# H15R80.net
KiCad netlist of a schematic drawn in EAGLE
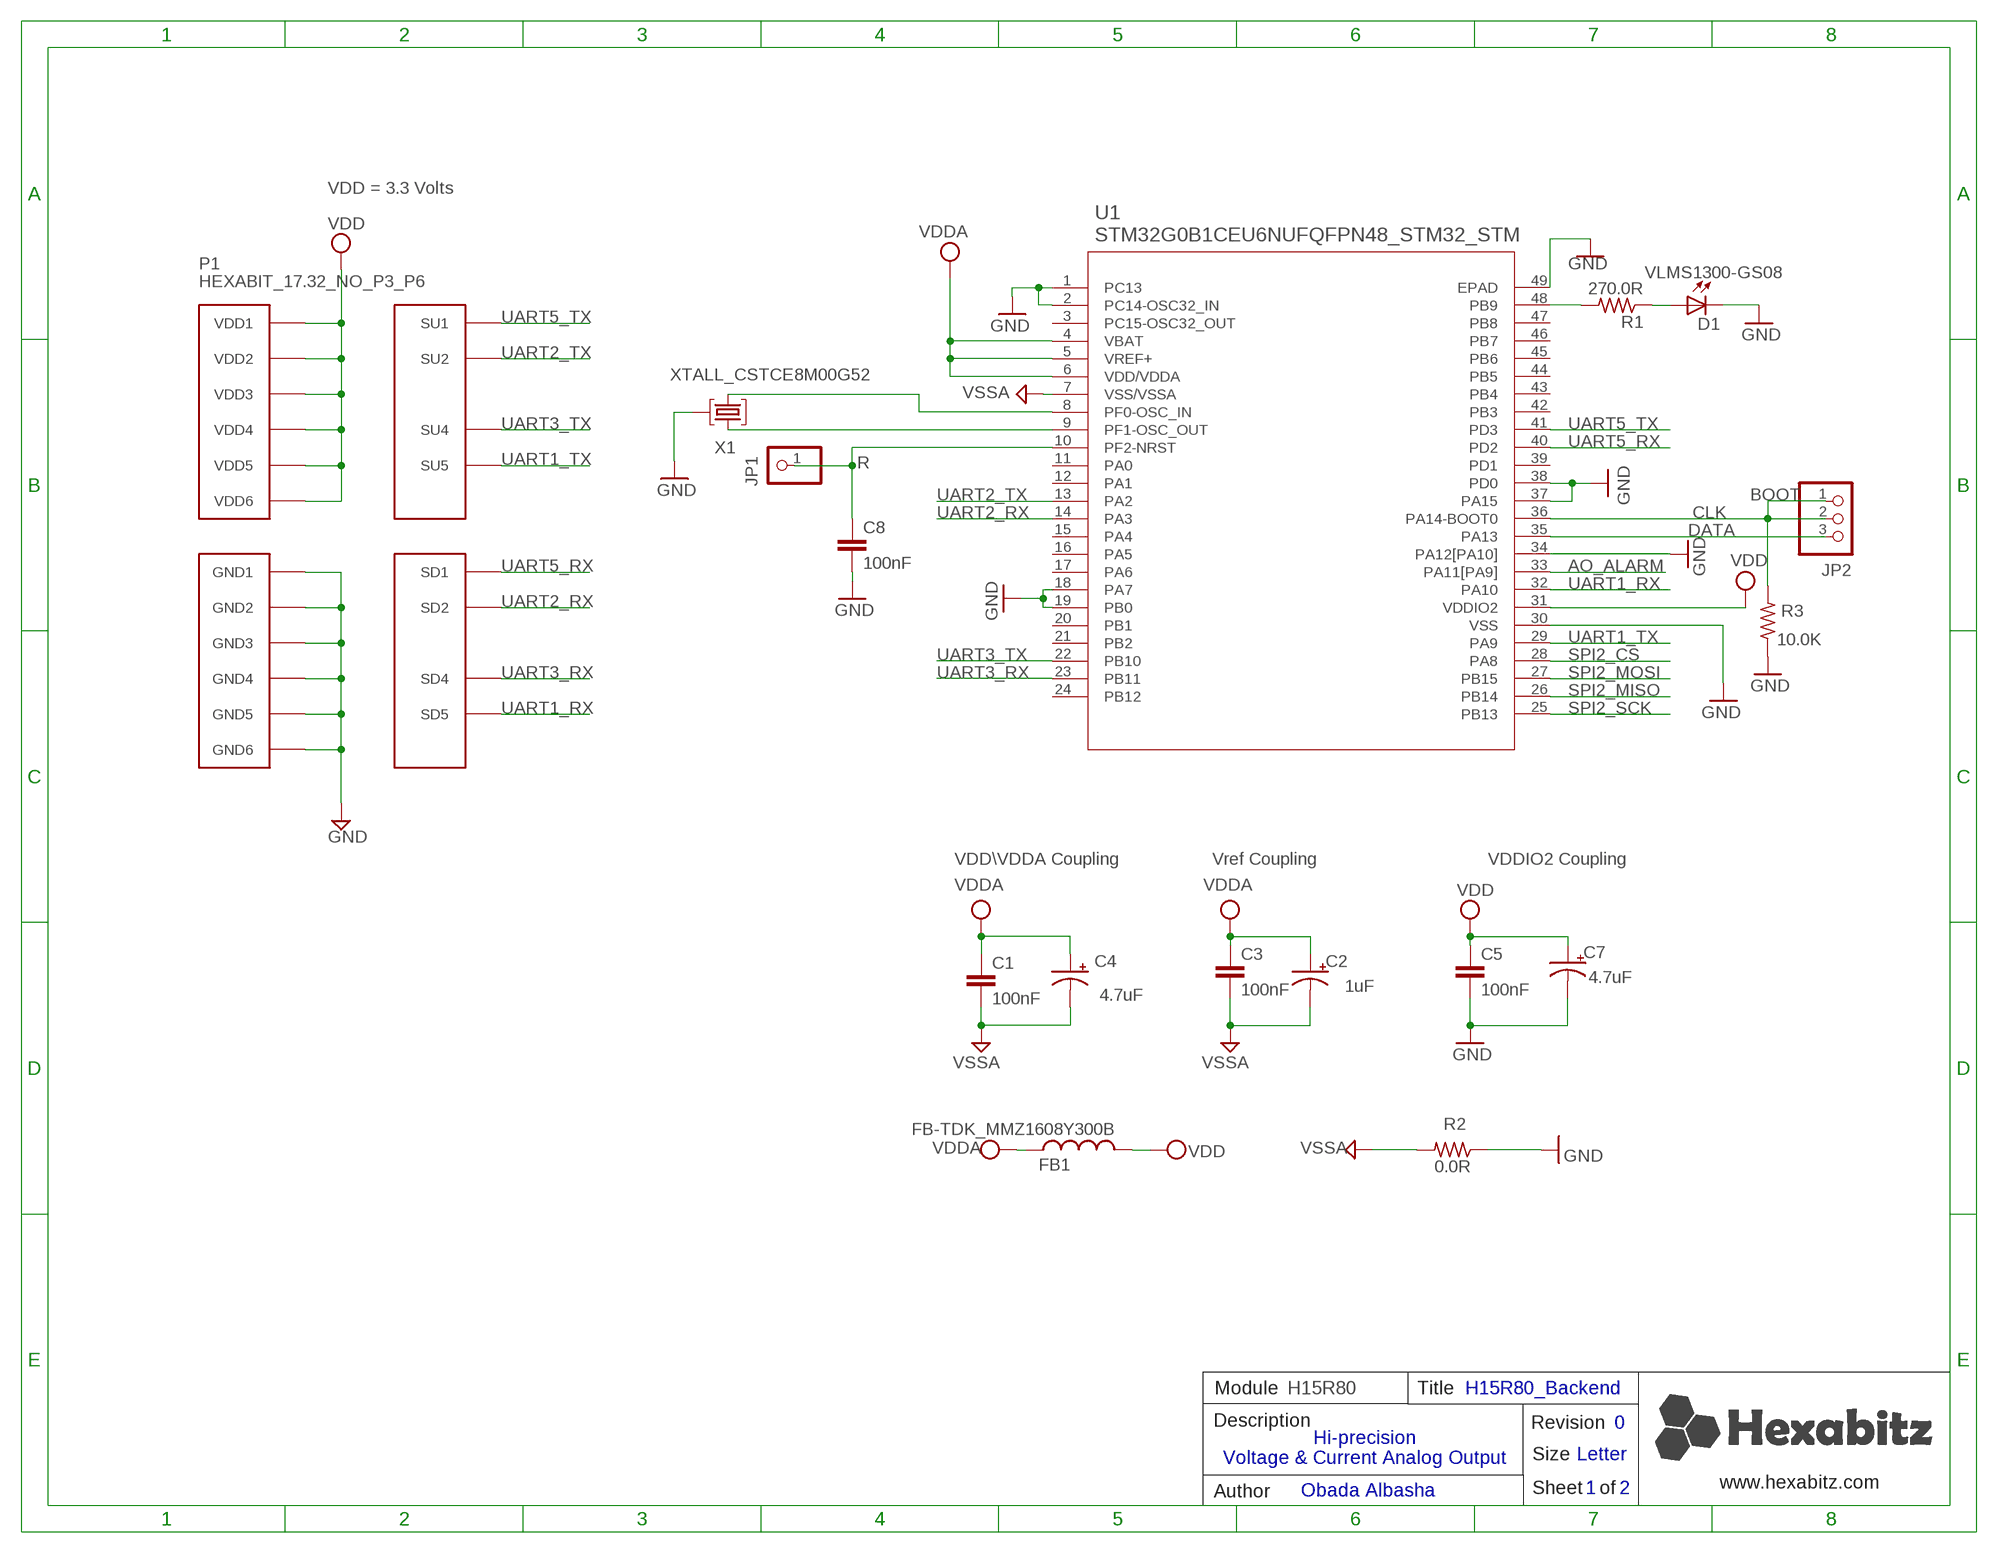
[diagram p0: schematic, sheet 1]
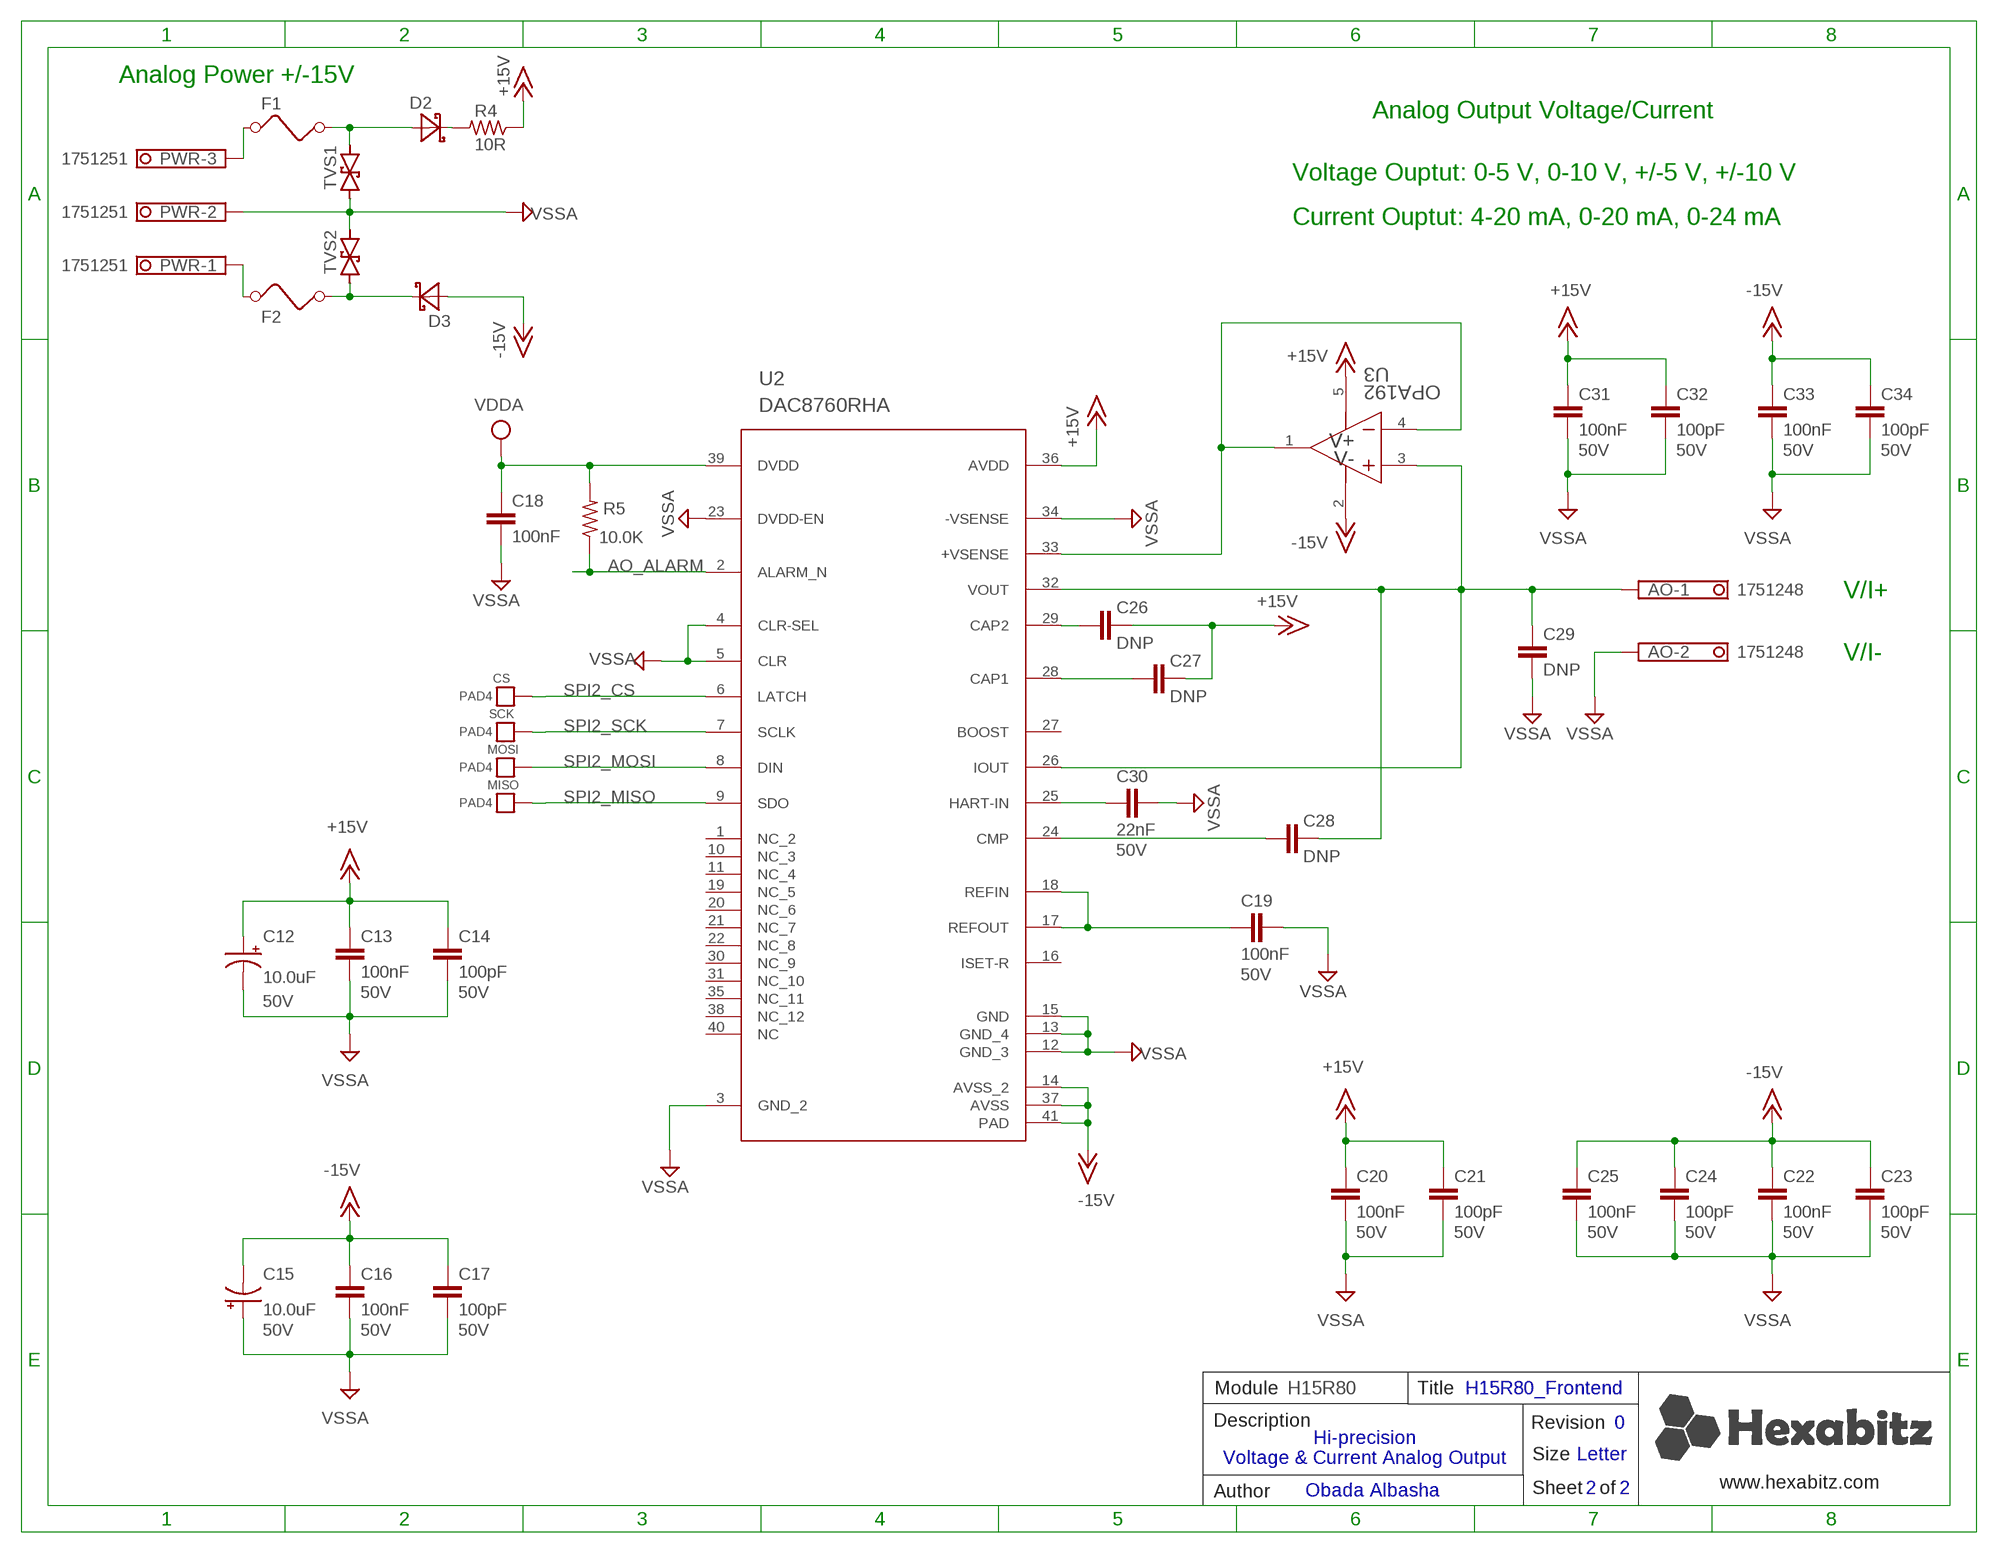
[diagram p1: schematic, sheet 2]

(export (version "E")
  (design (tool "Eeschema 10.0.6"))
  (components
    (comp (ref "C1")
      (value "100nF")
      (footprint "eagle-import:C-0603")
      (fields
        (field (name "CAPACITANCE") "10nF")
        (field (name "MFN") "KEMET")
        (field (name "MPN") "C0603C103K5RACTU")
        (field (name "OCTOPART_URL") "https://octopart.com/c0603c103k5ractu-kemet-133094?r=sp&s=R_iPBxLnSmGqhkU2rIMFpg")
        (field (name "TOLERANCE") "10%")
        (field (name "VOLTAGE_RATING") "50V")
      )
      (libsource (lib "eagle-import") (part "C-0603"))
    )
    (comp (ref "C2")
      (value "1uF")
      (footprint "eagle-import:C-0805-POL")
      (fields
        (field (name "CAPACITANCE") "4.7uF")
        (field (name "MFN") "Murata")
        (field (name "MPN") "GRM21BC81E475KA12L")
        (field (name "OCTOPART_URL") "https://octopart.com/grm21bc81e475ka12l-murata-10331911?r=sp&s=RY3qZSD8T6mG6TC9CHI5qQ")
        (field (name "TOLERANCE") "10%")
        (field (name "VOLTAGE_RATING") "25V")
      )
      (libsource (lib "eagle-import") (part "C-0805-POL"))
    )
    (comp (ref "C3")
      (value "100nF")
      (footprint "eagle-import:C-0603")
      (fields
        (field (name "CAPACITANCE") "100nF")
        (field (name "MFN") "KEMET")
        (field (name "MPN") "C0603C104K8RACTU")
        (field (name "OCTOPART_URL") "https://octopart.com/c0603c104k8ractu-kemet-145075?r=sp&s=9bS9ASSwSEqMCE9KBEQZ0g")
        (field (name "TOLERANCE") "10%")
        (field (name "VOLTAGE_RATING") "10V")
      )
      (libsource (lib "eagle-import") (part "C-0603"))
    )
    (comp (ref "C4")
      (value "4.7uF")
      (footprint "eagle-import:C-0805-POL")
      (fields
        (field (name "CAPACITANCE") "1.00uF")
        (field (name "MFN") "Yageo")
        (field (name "MPN") "CC0805KKX7R7BB105")
        (field (name "OCTOPART_URL") "https://octopart.com/cc0805kkx7r7bb105-yageo-8376555?r=sp&s=YKl1wwtkROau_X5nniH2ig")
        (field (name "TOLERANCE") "10%")
        (field (name "VOLTAGE_RATING") "16V")
      )
      (libsource (lib "eagle-import") (part "C-0805-POL"))
    )
    (comp (ref "C5")
      (value "100nF")
      (footprint "eagle-import:C-0603")
      (fields
        (field (name "CAPACITANCE") "100nF")
        (field (name "MFN") "KEMET")
        (field (name "MPN") "C0603C104K8RACTU")
        (field (name "OCTOPART_URL") "https://octopart.com/c0603c104k8ractu-kemet-145075?r=sp&s=9bS9ASSwSEqMCE9KBEQZ0g")
        (field (name "TOLERANCE") "10%")
        (field (name "VOLTAGE_RATING") "10")
      )
      (libsource (lib "eagle-import") (part "C-0603"))
    )
    (comp (ref "C7")
      (value "4.7uF")
      (footprint "eagle-import:C-0805-POL")
      (fields
        (field (name "CAPACITANCE") "4.7uF")
        (field (name "MFN") "Murata")
        (field (name "MPN") "GRM21BC81E475KA12L")
        (field (name "OCTOPART_URL") "https://octopart.com/grm21bc81e475ka12l-murata-10331911?r=sp&s=RY3qZSD8T6mG6TC9CHI5qQ")
        (field (name "TOLERANCE") "10%")
        (field (name "VOLTAGE_RATING") "25V")
      )
      (libsource (lib "eagle-import") (part "C-0805-POL"))
    )
    (comp (ref "C8")
      (value "100nF")
      (footprint "eagle-import:C-0603")
      (fields
        (field (name "CAPACITANCE") "100nF")
        (field (name "MFN") "KEMET")
        (field (name "MPN") "C0603C104K8RACTU")
        (field (name "OCTOPART_URL") "https://octopart.com/c0603c104k8ractu-kemet-145075?r=sp&s=9bS9ASSwSEqMCE9KBEQZ0g")
        (field (name "TOLERANCE") "10%")
        (field (name "VOLTAGE_RATING") "10V")
      )
      (libsource (lib "eagle-import") (part "C-0603"))
    )
    (comp (ref "D1")
      (value "VLMS1300-GS08")
      (footprint "eagle-import:VLMS1300-GS08")
      (fields
        (field (name "MFN") "Vishay")
        (field (name "MPN") "VLMS1300-GS08")
        (field (name "OCTOPART_URL") "https://octopart.com/vlms1300-gs08-vishay-21709201?r=sp&s=_gcP4_q8T1SC6PJQPTQ9yA")
      )
      (libsource (lib "eagle-import") (part "VLMS1300-GS08"))
    )
    (comp (ref "FB1")
      (value "FB-TDK_MMZ1608Y300B")
      (footprint "eagle-import:FB-TDK_MMZ1608Y300B")
      (fields
        (field (name "MFN") "TDK ")
        (field (name "MPN") "MMZ1608Y300B")
        (field (name "OCTOPART_URL") "https://octopart.com/mmz1608y300b-tdk-368280?r=sp&s=cd9_2ZEqQ9q9UNBuQgHAiA")
      )
      (libsource (lib "eagle-import") (part "FB-TDK_MMZ1608Y300B"))
    )
    (comp (ref "JP1")
      (value "R")
      (footprint "eagle-import:1X01")
      (fields (field (name "MPN") "87227-1"))
      (libsource (lib "eagle-import") (part "PINHD-1X1"))
    )
    (comp (ref "JP2")
      (value "PINHD-1X3")
      (footprint "eagle-import:1X03")
      (libsource (lib "eagle-import") (part "PINHD-1X3"))
    )
    (comp (ref "P1")
      (value "HEXABIT_17.32_NO_P3_P6")
      (footprint "eagle-import:HEXABIT_17.32_NO_P3_P6")
      (libsource (lib "eagle-import") (part "HEXABIT_?_NO_P3_P617.32"))
    )
    (comp (ref "R1")
      (value "270.0R")
      (footprint "eagle-import:R-0603")
      (fields
        (field (name "MFN") "Yageo")
        (field (name "MPN") "RC0603FR-07270RL")
        (field (name "OCTOPART_URL") "https://octopart.com/search?q=RC0603FR-07270RL&start=0")
        (field (name "RESISTANCE") "270.0 Ohm")
        (field (name "TOLERANCE") "1%")
      )
      (libsource (lib "eagle-import") (part "R-0603"))
    )
    (comp (ref "R2")
      (value "0.0R")
      (footprint "eagle-import:R-0603")
      (fields
        (field (name "MFN") "Yageo")
        (field (name "MPN") "RC0603JR-070RL")
        (field (name "OCTOPART_URL") "https://octopart.com/rc0603jr-070rl-yageo-1241539?r=sp&s=X2NteqRjRNWrnx42Y0aliA")
        (field (name "RESISTANCE") "0.0 Ohm")
      )
      (libsource (lib "eagle-import") (part "R-0603"))
    )
    (comp (ref "R3")
      (value "10.0K")
      (footprint "eagle-import:R-0603")
      (fields
        (field (name "MFN") "Yageo")
        (field (name "MPN") "RC0603JR-0710KL")
        (field (name "OCTOPART_URL") "https://octopart.com/search?q=RC0603JR-0710KL&start=0")
        (field (name "RESISTANCE") "10.0K Ohm")
        (field (name "TOLERANCE") "5%")
      )
      (libsource (lib "eagle-import") (part "R-0603"))
    )
    (comp (ref "U1")
      (value "STM32G0B1CEU6NUFQFPN48_STM32_STM")
      (footprint "eagle-import:UFQFPN48_STM32_STM")
      (fields
        (field (name "MPN") "STM32G0B1CEU6N")
        (field (name "COPYRIGHT") "Copyright (C) 2022 Ultra Librarian. All rights reserved.")
      )
      (libsource (lib "eagle-import") (part "STM32G0B1CEU6NUFQFPN48_STM32_STM"))
    )
    (comp (ref "X1")
      (value "XTALL_CSTCE8M00G52")
      (footprint "eagle-import:XTALL_CSTCE8M00G52")
      (fields (field (name "MPN") "CSTCE8M00G52Z-R0"))
      (libsource (lib "eagle-import") (part "XTALL_CSTCE8M00G52"))
    )
    (comp (ref "AO")
      (value "1751248")
      (footprint "eagle-import:1751248")
      (fields
        (field (name "MPN") "1751248")
        (field (name "MFN") "Phoenix Contact")
        (field (name "OCTOPART_URL") "https://octopart.com/1751248-phoenix+contact-31334?r=sp&s=dfbEyNHiQNetUL69ahOrPQ ")
      )
      (libsource (lib "eagle-import") (part "1751248"))
    )
    (comp (ref "C12")
      (value "10.0uF")
      (footprint "eagle-import:CT7343")
      (fields (field (name "MPN") "T491D106K050AT") (field (name "VOLTAGE") "50V"))
      (libsource (lib "eagle-import") (part "CPOL-USCT7343"))
    )
    (comp (ref "C13")
      (value "100nF")
      (footprint "eagle-import:C-0603")
      (fields
        (field (name "CAPACITANCE") "100nF")
        (field (name "MFN") "Samsung")
        (field (name "MPN") "CL10B104KB8NNNC")
        (field (name "OCTOPART_URL") "https://octopart.com/cl10b104kb8nnnc-samsung-7928277?r=sp&s=fIKkgin8S22eXTUxF1gXsw")
        (field (name "TOLERANCE") "10%")
        (field (name "VOLTAGE_RATING") "50V")
      )
      (libsource (lib "eagle-import") (part "C-0603"))
    )
    (comp (ref "C14")
      (value "100pF")
      (footprint "eagle-import:C-0603")
      (fields
        (field (name "CAPACITANCE") "100pF")
        (field (name "MFN") "Avx")
        (field (name "MPN") "06035A101JAT2A")
        (field (name "OCTOPART_URL") "https://octopart.com/06035a101jat2a-avx-55386344?r=sp&s=WDfgRo-ITV2A4U5JT5ZyKQ")
        (field (name "TOLERANCE") "10%")
        (field (name "VOLTAGE_RATING") "50V")
      )
      (libsource (lib "eagle-import") (part "C-0603"))
    )
    (comp (ref "C15")
      (value "10.0uF")
      (footprint "eagle-import:CT7343")
      (fields (field (name "MPN") "T491D106K050AT") (field (name "VOLTAGE") "50V"))
      (libsource (lib "eagle-import") (part "CPOL-USCT7343"))
    )
    (comp (ref "C16")
      (value "100nF")
      (footprint "eagle-import:C-0603")
      (fields
        (field (name "CAPACITANCE") "100nF")
        (field (name "MFN") "Samsung")
        (field (name "MPN") "CL10B104KB8NNNC")
        (field (name "OCTOPART_URL") "https://octopart.com/cl10b104kb8nnnc-samsung-7928277?r=sp&s=fIKkgin8S22eXTUxF1gXsw")
        (field (name "TOLERANCE") "10%")
        (field (name "VOLTAGE_RATING") "50V")
      )
      (libsource (lib "eagle-import") (part "C-0603"))
    )
    (comp (ref "C17")
      (value "100pF")
      (footprint "eagle-import:C-0603")
      (fields
        (field (name "CAPACITANCE") "100pF")
        (field (name "MFN") "Avx")
        (field (name "MPN") "06035A101JAT2A")
        (field (name "OCTOPART_URL") "https://octopart.com/06035a101jat2a-avx-55386344?r=sp&s=WDfgRo-ITV2A4U5JT5ZyKQ")
        (field (name "TOLERANCE") "10%")
        (field (name "VOLTAGE_RATING") "50V")
      )
      (libsource (lib "eagle-import") (part "C-0603"))
    )
    (comp (ref "C18")
      (value "100nF")
      (footprint "eagle-import:C-0603")
      (fields
        (field (name "CAPACITANCE") "100nF")
        (field (name "MFN") "KEMET")
        (field (name "MPN") "C0603C104K8RACTU")
        (field (name "OCTOPART_URL") "https://octopart.com/c0603c104k8ractu-kemet-145075?r=sp&s=9bS9ASSwSEqMCE9KBEQZ0g")
        (field (name "TOLERANCE") "10%")
        (field (name "VOLTAGE_RATING") "10V")
      )
      (libsource (lib "eagle-import") (part "C-0603"))
    )
    (comp (ref "C19")
      (value "100nF")
      (footprint "eagle-import:C-0603")
      (fields
        (field (name "CAPACITANCE") "100nF")
        (field (name "MFN") "Samsung")
        (field (name "MPN") "CL10B104KB8NNNC")
        (field (name "OCTOPART_URL") "https://octopart.com/cl10b104kb8nnnc-samsung-7928277?r=sp&s=fIKkgin8S22eXTUxF1gXsw")
        (field (name "TOLERANCE") "10%")
        (field (name "VOLTAGE_RATING") "50V")
      )
      (libsource (lib "eagle-import") (part "C-0603"))
    )
    (comp (ref "C20")
      (value "100nF")
      (footprint "eagle-import:C-0603")
      (fields
        (field (name "CAPACITANCE") "100nF")
        (field (name "MFN") "Samsung")
        (field (name "MPN") "CL10B104KB8NNNC")
        (field (name "OCTOPART_URL") "https://octopart.com/cl10b104kb8nnnc-samsung-7928277?r=sp&s=fIKkgin8S22eXTUxF1gXsw")
        (field (name "TOLERANCE") "10%")
        (field (name "VOLTAGE_RATING") "50V")
      )
      (libsource (lib "eagle-import") (part "C-0603"))
    )
    (comp (ref "C21")
      (value "100pF")
      (footprint "eagle-import:C-0603")
      (fields
        (field (name "CAPACITANCE") "100pF")
        (field (name "MFN") "Avx")
        (field (name "MPN") "06035A101JAT2A")
        (field (name "OCTOPART_URL") "https://octopart.com/06035a101jat2a-avx-55386344?r=sp&s=WDfgRo-ITV2A4U5JT5ZyKQ")
        (field (name "TOLERANCE") "10%")
        (field (name "VOLTAGE_RATING") "50V")
      )
      (libsource (lib "eagle-import") (part "C-0603"))
    )
    (comp (ref "C22")
      (value "100nF")
      (footprint "eagle-import:C-0603")
      (fields
        (field (name "CAPACITANCE") "100nF")
        (field (name "MFN") "Samsung")
        (field (name "MPN") "CL10B104KB8NNNC")
        (field (name "OCTOPART_URL") "https://octopart.com/cl10b104kb8nnnc-samsung-7928277?r=sp&s=fIKkgin8S22eXTUxF1gXsw")
        (field (name "TOLERANCE") "10%")
        (field (name "VOLTAGE_RATING") "50V")
      )
      (libsource (lib "eagle-import") (part "C-0603"))
    )
    (comp (ref "C23")
      (value "100pF")
      (footprint "eagle-import:C-0603")
      (fields
        (field (name "CAPACITANCE") "100pF")
        (field (name "MFN") "Avx")
        (field (name "MPN") "06035A101JAT2A")
        (field (name "OCTOPART_URL") "https://octopart.com/06035a101jat2a-avx-55386344?r=sp&s=WDfgRo-ITV2A4U5JT5ZyKQ")
        (field (name "TOLERANCE") "10%")
        (field (name "VOLTAGE_RATING") "50V")
      )
      (libsource (lib "eagle-import") (part "C-0603"))
    )
    (comp (ref "C24")
      (value "100pF")
      (footprint "eagle-import:C-0603")
      (fields
        (field (name "CAPACITANCE") "100pF")
        (field (name "MFN") "Avx")
        (field (name "MPN") "06035A101JAT2A")
        (field (name "OCTOPART_URL") "https://octopart.com/06035a101jat2a-avx-55386344?r=sp&s=WDfgRo-ITV2A4U5JT5ZyKQ")
        (field (name "TOLERANCE") "10%")
        (field (name "VOLTAGE_RATING") "50V")
      )
      (libsource (lib "eagle-import") (part "C-0603"))
    )
    (comp (ref "C25")
      (value "100nF")
      (footprint "eagle-import:C-0603")
      (fields
        (field (name "CAPACITANCE") "100nF")
        (field (name "MFN") "Samsung")
        (field (name "MPN") "CL10B104KB8NNNC")
        (field (name "OCTOPART_URL") "https://octopart.com/cl10b104kb8nnnc-samsung-7928277?r=sp&s=fIKkgin8S22eXTUxF1gXsw")
        (field (name "TOLERANCE") "10%")
        (field (name "VOLTAGE_RATING") "50V")
      )
      (libsource (lib "eagle-import") (part "C-0603"))
    )
    (comp (ref "C26")
      (value "DNP")
      (footprint "eagle-import:C-0603")
      (fields (field (name "CAPACITANCE") "DNP") (field (name "MPN") "DNP"))
      (libsource (lib "eagle-import") (part "C-0603"))
    )
    (comp (ref "C27")
      (value "DNP")
      (footprint "eagle-import:C-0603")
      (fields (field (name "CAPACITANCE") "DNP") (field (name "MPN") "DNP"))
      (libsource (lib "eagle-import") (part "C-0603"))
    )
    (comp (ref "C28")
      (value "DNP")
      (footprint "eagle-import:C-0603")
      (fields (field (name "CAPACITANCE") "DNP") (field (name "MPN") "DNP"))
      (libsource (lib "eagle-import") (part "C-0603"))
    )
    (comp (ref "C29")
      (value "DNP")
      (footprint "eagle-import:C-0603")
      (fields (field (name "CAPACITANCE") "DNP") (field (name "MPN") "DNP"))
      (libsource (lib "eagle-import") (part "C-0603"))
    )
    (comp (ref "C30")
      (value "22nF")
      (footprint "eagle-import:C-0603")
      (fields
        (field (name "CAPACITANCE") "22nF")
        (field (name "MFN") "TDK")
        (field (name "MPN") "C1608X7R1H223K080AA")
        (field (name "OCTOPART_URL") "https://octopart.com/c1608x7r1h223k080aa-tdk-25947667?r=sp&s=T8cT_uRxS7ewuHBmxCxszg")
        (field (name "TOLERANCE") "10%")
        (field (name "VOLTAGE_RATING") "50V")
      )
      (libsource (lib "eagle-import") (part "C-0603"))
    )
    (comp (ref "C31")
      (value "100nF")
      (footprint "eagle-import:C-0603")
      (fields
        (field (name "CAPACITANCE") "100nF")
        (field (name "MFN") "Samsung")
        (field (name "MPN") "CL10B104KB8NNNC")
        (field (name "OCTOPART_URL") "https://octopart.com/cl10b104kb8nnnc-samsung-7928277?r=sp&s=fIKkgin8S22eXTUxF1gXsw")
        (field (name "TOLERANCE") "10%")
        (field (name "VOLTAGE_RATING") "50V")
      )
      (libsource (lib "eagle-import") (part "C-0603"))
    )
    (comp (ref "C32")
      (value "100pF")
      (footprint "eagle-import:C-0603")
      (fields
        (field (name "CAPACITANCE") "100pF")
        (field (name "MFN") "Avx")
        (field (name "MPN") "06035A101JAT2A")
        (field (name "OCTOPART_URL") "https://octopart.com/06035a101jat2a-avx-55386344?r=sp&s=WDfgRo-ITV2A4U5JT5ZyKQ")
        (field (name "TOLERANCE") "10%")
        (field (name "VOLTAGE_RATING") "50V")
      )
      (libsource (lib "eagle-import") (part "C-0603"))
    )
    (comp (ref "C33")
      (value "100nF")
      (footprint "eagle-import:C-0603")
      (fields
        (field (name "CAPACITANCE") "100nF")
        (field (name "MFN") "Samsung")
        (field (name "MPN") "CL10B104KB8NNNC")
        (field (name "OCTOPART_URL") "https://octopart.com/cl10b104kb8nnnc-samsung-7928277?r=sp&s=fIKkgin8S22eXTUxF1gXsw")
        (field (name "TOLERANCE") "10%")
        (field (name "VOLTAGE_RATING") "50V")
      )
      (libsource (lib "eagle-import") (part "C-0603"))
    )
    (comp (ref "C34")
      (value "100pF")
      (footprint "eagle-import:C-0603")
      (fields
        (field (name "CAPACITANCE") "100pF")
        (field (name "MFN") "Avx")
        (field (name "MPN") "06035A101JAT2A")
        (field (name "OCTOPART_URL") "https://octopart.com/06035a101jat2a-avx-55386344?r=sp&s=WDfgRo-ITV2A4U5JT5ZyKQ")
        (field (name "TOLERANCE") "10%")
        (field (name "VOLTAGE_RATING") "50V")
      )
      (libsource (lib "eagle-import") (part "C-0603"))
    )
    (comp (ref "CS")
      (value "PAD4")
      (footprint "eagle-import:PAD4")
      (libsource (lib "eagle-import") (part "PAD4"))
    )
    (comp (ref "D2")
      (value "DIOD-SOD-123")
      (footprint "eagle-import:SOD123")
      (libsource (lib "eagle-import") (part "DIOD-SOD-123"))
    )
    (comp (ref "D3")
      (value "DIOD-SOD-123")
      (footprint "eagle-import:SOD123")
      (libsource (lib "eagle-import") (part "DIOD-SOD-123"))
    )
    (comp (ref "F1")
      (value "NANOSMDC035F-2120")
      (footprint "eagle-import:R1206")
      (fields (field (name "MPN") "NANOSMDC035F-2"))
      (libsource (lib "eagle-import") (part "NANOSMDC035F-2120"))
    )
    (comp (ref "F2")
      (value "NANOSMDC035F-2120")
      (footprint "eagle-import:R1206")
      (fields (field (name "MPN") "NANOSMDC035F-2"))
      (libsource (lib "eagle-import") (part "NANOSMDC035F-2120"))
    )
    (comp (ref "MISO")
      (value "PAD4")
      (footprint "eagle-import:PAD4")
      (libsource (lib "eagle-import") (part "PAD4"))
    )
    (comp (ref "MOSI")
      (value "PAD4")
      (footprint "eagle-import:PAD4")
      (libsource (lib "eagle-import") (part "PAD4"))
    )
    (comp (ref "PWR")
      (value "1751251")
      (footprint "eagle-import:1751251")
      (fields
        (field (name "MFN") "Phoenix Contact")
        (field (name "MPN") "1751251")
        (field (name "OCTOPART_URL") "https://octopart.com/1751251-phoenix+contact-36473?r=sp&s=9M0VWNoHTyq04j3qI6lQOQ ")
      )
      (libsource (lib "eagle-import") (part "1751251"))
    )
    (comp (ref "R4")
      (value "10R")
      (footprint "eagle-import:R-0603")
      (fields
        (field (name "MFN") "Yageo")
        (field (name "MPN") "RC0603JR-0710KL")
        (field (name "OCTOPART_URL") "https://octopart.com/search?q=RC0603JR-0710KL&start=0")
        (field (name "RESISTANCE") "10.0K Ohm")
        (field (name "TOLERANCE") "5%")
      )
      (libsource (lib "eagle-import") (part "R-0603"))
    )
    (comp (ref "R5")
      (value "10.0K")
      (footprint "eagle-import:R-0603")
      (fields
        (field (name "MFN") "Yageo")
        (field (name "MPN") "RC0603JR-0710KL")
        (field (name "OCTOPART_URL") "https://octopart.com/search?q=RC0603JR-0710KL&start=0")
        (field (name "RESISTANCE") "10.0K Ohm")
        (field (name "TOLERANCE") "5%")
      )
      (libsource (lib "eagle-import") (part "R-0603"))
    )
    (comp (ref "SCK")
      (value "PAD4")
      (footprint "eagle-import:PAD4")
      (libsource (lib "eagle-import") (part "PAD4"))
    )
    (comp (ref "TVS1")
      (value "SMBJ30CA")
      (footprint "eagle-import:DO214AA")
      (libsource (lib "eagle-import") (part "SMBJ30CA"))
    )
    (comp (ref "TVS2")
      (value "SMBJ30CA")
      (footprint "eagle-import:DO214AA")
      (libsource (lib "eagle-import") (part "SMBJ30CA"))
    )
    (comp (ref "U2")
      (value "DAC8760RHA")
      (footprint "eagle-import:RHA0040A")
      (fields
        (field (name "MANUFACTURER") "Texas Instruments")
        (field (name "MPN") "DAC8760IRHAR")
        (field (name "PARTNUMBER") "DAC7760IRHAR")
      )
      (libsource (lib "eagle-import") (part "DAC7760IRHAR"))
    )
    (comp (ref "U3")
      (value "OPA192")
      (footprint "eagle-import:DBV0005A_N")
      (fields
        (field (name "ALTERNATE_PARTNUMBER") "OPA192IDBVT")
        (field (name "MANUFACTURER") "Texas Instruments")
        (field (name "PARTNUMBER") "OPA192IDBVR")
      )
      (libsource (lib "eagle-import") (part "OPA192IDBVR"))
    )
  )
  (nets
    (net (code "1") (name "+15V") (class "Default")
      (node (ref "C12") (pin "+") (pinfunction "+_+") (pintype "passive"))
      (node (ref "C13") (pin "1") (pinfunction "1_1") (pintype "passive"))
      (node (ref "C14") (pin "1") (pinfunction "1_1") (pintype "passive"))
      (node (ref "C20") (pin "1") (pinfunction "1_1") (pintype "passive"))
      (node (ref "C21") (pin "1") (pinfunction "1_1") (pintype "passive"))
      (node (ref "C26") (pin "2") (pinfunction "2_2") (pintype "passive"))
      (node (ref "C27") (pin "2") (pinfunction "2_2") (pintype "passive"))
      (node (ref "C31") (pin "1") (pinfunction "1_1") (pintype "passive"))
      (node (ref "C32") (pin "1") (pinfunction "1_1") (pintype "passive"))
      (node (ref "R4") (pin "1") (pinfunction "1_1") (pintype "passive"))
      (node (ref "U2") (pin "36") (pinfunction "AVDD_36") (pintype "power_in"))
      (node (ref "U3") (pin "5") (pinfunction "V+_5") (pintype "power_in"))
    )
    (net (code "2") (name "-15V") (class "Default")
      (node (ref "C15") (pin "-") (pinfunction "-_-") (pintype "passive"))
      (node (ref "C16") (pin "1") (pinfunction "1_1") (pintype "passive"))
      (node (ref "C17") (pin "1") (pinfunction "1_1") (pintype "passive"))
      (node (ref "C22") (pin "1") (pinfunction "1_1") (pintype "passive"))
      (node (ref "C23") (pin "1") (pinfunction "1_1") (pintype "passive"))
      (node (ref "C24") (pin "1") (pinfunction "1_1") (pintype "passive"))
      (node (ref "C25") (pin "1") (pinfunction "1_1") (pintype "passive"))
      (node (ref "C33") (pin "1") (pinfunction "1_1") (pintype "passive"))
      (node (ref "C34") (pin "1") (pinfunction "1_1") (pintype "passive"))
      (node (ref "D3") (pin "1") (pinfunction "A_1") (pintype "passive"))
      (node (ref "U2") (pin "14") (pinfunction "AVSS_2_14") (pintype "power_in"))
      (node (ref "U2") (pin "37") (pinfunction "AVSS_37") (pintype "power_in"))
      (node (ref "U2") (pin "41") (pinfunction "PAD_41") (pintype "power_in"))
      (node (ref "U3") (pin "2") (pinfunction "V-_2") (pintype "power_in"))
    )
    (net (code "3") (name "AO_ALARM") (class "Default")
      (node (ref "R5") (pin "1") (pinfunction "1_1") (pintype "passive"))
      (node (ref "U1") (pin "33") (pinfunction "PA11[PA9]_33") (pintype "bidirectional"))
      (node (ref "U2") (pin "2") (pinfunction "ALARM_N_2") (pintype "open_collector"))
    )
    (net (code "4") (name "CLK") (class "Default")
      (node (ref "JP2") (pin "1") (pinfunction "1_1") (pintype "passive"))
      (node (ref "JP2") (pin "2") (pinfunction "2_2") (pintype "passive"))
      (node (ref "R3") (pin "2") (pinfunction "2_2") (pintype "passive"))
      (node (ref "U1") (pin "36") (pinfunction "PA14-BOOT0_36") (pintype "bidirectional"))
    )
    (net (code "5") (name "DATA") (class "Default")
      (node (ref "JP2") (pin "3") (pinfunction "3_3") (pintype "passive"))
      (node (ref "U1") (pin "35") (pinfunction "PA13_35") (pintype "bidirectional"))
    )
    (net (code "6") (name "GND") (class "Default")
      (node (ref "C5") (pin "2") (pinfunction "2_2") (pintype "passive"))
      (node (ref "C7") (pin "2") (pinfunction "-_2") (pintype "passive"))
      (node (ref "C8") (pin "2") (pinfunction "2_2") (pintype "passive"))
      (node (ref "D1") (pin "C") (pinfunction "C_C") (pintype "passive"))
      (node (ref "P1") (pin "PAD_PD10") (pinfunction "GND4_PAD_PD10") (pintype "power_in"))
      (node (ref "P1") (pin "PAD_PD11") (pinfunction "GND5_PAD_PD11") (pintype "power_in"))
      (node (ref "P1") (pin "PAD_PD12") (pinfunction "GND6_PAD_PD12") (pintype "power_in"))
      (node (ref "P1") (pin "PAD_PD7") (pinfunction "GND1_PAD_PD7") (pintype "power_in"))
      (node (ref "P1") (pin "PAD_PD8") (pinfunction "GND2_PAD_PD8") (pintype "power_in"))
      (node (ref "P1") (pin "PAD_PD9") (pinfunction "GND3_PAD_PD9") (pintype "power_in"))
      (node (ref "R2") (pin "1") (pinfunction "1_1") (pintype "passive"))
      (node (ref "R3") (pin "1") (pinfunction "1_1") (pintype "passive"))
      (node (ref "U1") (pin "1") (pinfunction "PC13_1") (pintype "bidirectional"))
      (node (ref "U1") (pin "18") (pinfunction "PA7_18") (pintype "bidirectional"))
      (node (ref "U1") (pin "19") (pinfunction "PB0_19") (pintype "bidirectional"))
      (node (ref "U1") (pin "2") (pinfunction "PC14-OSC32_IN_2") (pintype "bidirectional"))
      (node (ref "U1") (pin "30") (pinfunction "VSS_30") (pintype "passive"))
      (node (ref "U1") (pin "34") (pinfunction "PA12[PA10]_34") (pintype "bidirectional"))
      (node (ref "U1") (pin "37") (pinfunction "PA15_37") (pintype "bidirectional"))
      (node (ref "U1") (pin "38") (pinfunction "PD0_38") (pintype "bidirectional"))
      (node (ref "U1") (pin "49") (pinfunction "EPAD_49") (pintype "passive"))
      (node (ref "X1") (pin "P$2") (pinfunction "2_P$2") (pintype "passive"))
    )
    (net (code "7") (name "Net-(AOA-K)") (class "Default")
      (node (ref "AO") (pin "1") (pinfunction "K_1") (pintype "passive"))
      (node (ref "C28") (pin "2") (pinfunction "2_2") (pintype "passive"))
      (node (ref "C29") (pin "2") (pinfunction "2_2") (pintype "passive"))
      (node (ref "U2") (pin "26") (pinfunction "IOUT_26") (pintype "output"))
      (node (ref "U2") (pin "32") (pinfunction "VOUT_32") (pintype "output"))
      (node (ref "U3") (pin "3") (pinfunction "IN+_3") (pintype "input"))
    )
    (net (code "8") (name "Net-(D1-PadA)") (class "Default")
      (node (ref "D1") (pin "A") (pinfunction "A_A") (pintype "passive"))
      (node (ref "R1") (pin "1") (pinfunction "1_1") (pintype "passive"))
    )
    (net (code "9") (name "Net-(D2-A)") (class "Default")
      (node (ref "D2") (pin "1") (pinfunction "A_1") (pintype "passive"))
      (node (ref "F1") (pin "2") (pinfunction "2_2") (pintype "passive"))
      (node (ref "TVS1") (pin "C") (pinfunction "2_C") (pintype "passive"))
    )
    (net (code "10") (name "Net-(D2-C)") (class "Default")
      (node (ref "D2") (pin "2") (pinfunction "C_2") (pintype "passive"))
      (node (ref "R4") (pin "2") (pinfunction "2_2") (pintype "passive"))
    )
    (net (code "11") (name "Net-(D3-C)") (class "Default")
      (node (ref "D3") (pin "2") (pinfunction "C_2") (pintype "passive"))
      (node (ref "F2") (pin "2") (pinfunction "2_2") (pintype "passive"))
      (node (ref "TVS2") (pin "A") (pinfunction "1_A") (pintype "passive"))
    )
    (net (code "12") (name "Net-(PWRA-K)") (class "Default")
      (node (ref "F2") (pin "1") (pinfunction "1_1") (pintype "passive"))
      (node (ref "PWR") (pin "1") (pinfunction "K_1") (pintype "passive"))
    )
    (net (code "13") (name "Net-(PWRC-K)") (class "Default")
      (node (ref "F1") (pin "1") (pinfunction "1_1") (pintype "passive"))
      (node (ref "PWR") (pin "3") (pinfunction "K_3") (pintype "passive"))
    )
    (net (code "14") (name "Net-(U1-PB9)") (class "Default")
      (node (ref "R1") (pin "2") (pinfunction "2_2") (pintype "passive"))
      (node (ref "U1") (pin "48") (pinfunction "PB9_48") (pintype "bidirectional"))
    )
    (net (code "15") (name "Net-(U1-PF0-OSC_IN)") (class "Default")
      (node (ref "U1") (pin "8") (pinfunction "PF0-OSC_IN_8") (pintype "bidirectional"))
      (node (ref "X1") (pin "P$3") (pinfunction "3_P$3") (pintype "passive"))
    )
    (net (code "16") (name "Net-(U1-PF1-OSC_OUT)") (class "Default")
      (node (ref "U1") (pin "9") (pinfunction "PF1-OSC_OUT_9") (pintype "bidirectional"))
      (node (ref "X1") (pin "P$1") (pinfunction "1_P$1") (pintype "passive"))
    )
    (net (code "17") (name "Net-(U1-PF2-NRST)") (class "Default")
      (node (ref "C8") (pin "1") (pinfunction "1_1") (pintype "passive"))
      (node (ref "JP1") (pin "1") (pinfunction "1_1") (pintype "passive"))
      (node (ref "U1") (pin "10") (pinfunction "PF2-NRST_10") (pintype "bidirectional"))
    )
    (net (code "18") (name "Net-(U2-+VSENSE)") (class "Default")
      (node (ref "U2") (pin "33") (pinfunction "+VSENSE_33") (pintype "input"))
      (node (ref "U3") (pin "1") (pinfunction "OUT_1") (pintype "output"))
      (node (ref "U3") (pin "4") (pinfunction "IN-_4") (pintype "input"))
    )
    (net (code "19") (name "Net-(U2-CAP1)") (class "Default")
      (node (ref "C27") (pin "1") (pinfunction "1_1") (pintype "passive"))
      (node (ref "U2") (pin "28") (pinfunction "CAP1_28") (pintype "input"))
    )
    (net (code "20") (name "Net-(U2-CAP2)") (class "Default")
      (node (ref "C26") (pin "1") (pinfunction "1_1") (pintype "passive"))
      (node (ref "U2") (pin "29") (pinfunction "CAP2_29") (pintype "input"))
    )
    (net (code "21") (name "Net-(U2-CMP)") (class "Default")
      (node (ref "C28") (pin "1") (pinfunction "1_1") (pintype "passive"))
      (node (ref "U2") (pin "24") (pinfunction "CMP_24") (pintype "input"))
    )
    (net (code "22") (name "Net-(U2-HART-IN)") (class "Default")
      (node (ref "C30") (pin "1") (pinfunction "1_1") (pintype "passive"))
      (node (ref "U2") (pin "25") (pinfunction "HART-IN_25") (pintype "input"))
    )
    (net (code "23") (name "Net-(U2-REFIN)") (class "Default")
      (node (ref "C19") (pin "1") (pinfunction "1_1") (pintype "passive"))
      (node (ref "U2") (pin "17") (pinfunction "REFOUT_17") (pintype "output"))
      (node (ref "U2") (pin "18") (pinfunction "REFIN_18") (pintype "input"))
    )
    (net (code "24") (name "SPI2_CS") (class "Default")
      (node (ref "CS") (pin "P$1") (pinfunction "P$1_P$1") (pintype "passive"))
      (node (ref "U1") (pin "28") (pinfunction "PA8_28") (pintype "bidirectional"))
      (node (ref "U2") (pin "6") (pinfunction "LATCH_6") (pintype "input"))
    )
    (net (code "25") (name "SPI2_MISO") (class "Default")
      (node (ref "MISO") (pin "P$1") (pinfunction "P$1_P$1") (pintype "passive"))
      (node (ref "U1") (pin "26") (pinfunction "PB14_26") (pintype "bidirectional"))
      (node (ref "U2") (pin "9") (pinfunction "SDO_9") (pintype "output"))
    )
    (net (code "26") (name "SPI2_MOSI") (class "Default")
      (node (ref "MOSI") (pin "P$1") (pinfunction "P$1_P$1") (pintype "passive"))
      (node (ref "U1") (pin "27") (pinfunction "PB15_27") (pintype "bidirectional"))
      (node (ref "U2") (pin "8") (pinfunction "DIN_8") (pintype "input"))
    )
    (net (code "27") (name "SPI2_SCK") (class "Default")
      (node (ref "SCK") (pin "P$1") (pinfunction "P$1_P$1") (pintype "passive"))
      (node (ref "U1") (pin "25") (pinfunction "PB13_25") (pintype "bidirectional"))
      (node (ref "U2") (pin "7") (pinfunction "SCLK_7") (pintype "input"))
    )
    (net (code "28") (name "UART1_RX") (class "Default")
      (node (ref "P1") (pin "PAD_PD5") (pinfunction "SD5_PAD_PD5") (pintype "bidirectional"))
      (node (ref "U1") (pin "32") (pinfunction "PA10_32") (pintype "bidirectional"))
    )
    (net (code "29") (name "UART1_TX") (class "Default")
      (node (ref "P1") (pin "PAD_PU5") (pinfunction "SU5_PAD_PU5") (pintype "bidirectional"))
      (node (ref "U1") (pin "29") (pinfunction "PA9_29") (pintype "bidirectional"))
    )
    (net (code "30") (name "UART2_RX") (class "Default")
      (node (ref "P1") (pin "PAD_PD2") (pinfunction "SD2_PAD_PD2") (pintype "bidirectional"))
      (node (ref "U1") (pin "14") (pinfunction "PA3_14") (pintype "bidirectional"))
    )
    (net (code "31") (name "UART2_TX") (class "Default")
      (node (ref "P1") (pin "PAD_PU2") (pinfunction "SU2_PAD_PU2") (pintype "bidirectional"))
      (node (ref "U1") (pin "13") (pinfunction "PA2_13") (pintype "bidirectional"))
    )
    (net (code "32") (name "UART3_RX") (class "Default")
      (node (ref "P1") (pin "PAD_PD4") (pinfunction "SD4_PAD_PD4") (pintype "bidirectional"))
      (node (ref "U1") (pin "23") (pinfunction "PB11_23") (pintype "bidirectional"))
    )
    (net (code "33") (name "UART3_TX") (class "Default")
      (node (ref "P1") (pin "PAD_PU4") (pinfunction "SU4_PAD_PU4") (pintype "bidirectional"))
      (node (ref "U1") (pin "22") (pinfunction "PB10_22") (pintype "bidirectional"))
    )
    (net (code "34") (name "UART5_RX") (class "Default")
      (node (ref "P1") (pin "PAD_PD1") (pinfunction "SD1_PAD_PD1") (pintype "bidirectional"))
      (node (ref "U1") (pin "40") (pinfunction "PD2_40") (pintype "bidirectional"))
    )
    (net (code "35") (name "UART5_TX") (class "Default")
      (node (ref "P1") (pin "PAD_PU1") (pinfunction "SU1_PAD_PU1") (pintype "bidirectional"))
      (node (ref "U1") (pin "41") (pinfunction "PD3_41") (pintype "bidirectional"))
    )
    (net (code "36") (name "VDD") (class "Default")
      (node (ref "C5") (pin "1") (pinfunction "1_1") (pintype "passive"))
      (node (ref "C7") (pin "1") (pinfunction "+_1") (pintype "passive"))
      (node (ref "FB1") (pin "2") (pinfunction "2_2") (pintype "passive"))
      (node (ref "P1") (pin "PAD_PU10") (pinfunction "VDD4_PAD_PU10") (pintype "power_in"))
      (node (ref "P1") (pin "PAD_PU11") (pinfunction "VDD5_PAD_PU11") (pintype "power_in"))
      (node (ref "P1") (pin "PAD_PU12") (pinfunction "VDD6_PAD_PU12") (pintype "power_in"))
      (node (ref "P1") (pin "PAD_PU7") (pinfunction "VDD1_PAD_PU7") (pintype "power_in"))
      (node (ref "P1") (pin "PAD_PU8") (pinfunction "VDD2_PAD_PU8") (pintype "power_in"))
      (node (ref "P1") (pin "PAD_PU9") (pinfunction "VDD3_PAD_PU9") (pintype "power_in"))
      (node (ref "U1") (pin "31") (pinfunction "VDDIO2_31") (pintype "power_in"))
    )
    (net (code "37") (name "VDDA") (class "Default")
      (node (ref "C1") (pin "1") (pinfunction "1_1") (pintype "passive"))
      (node (ref "C18") (pin "1") (pinfunction "1_1") (pintype "passive"))
      (node (ref "C2") (pin "1") (pinfunction "+_1") (pintype "passive"))
      (node (ref "C3") (pin "1") (pinfunction "1_1") (pintype "passive"))
      (node (ref "C4") (pin "1") (pinfunction "+_1") (pintype "passive"))
      (node (ref "FB1") (pin "1") (pinfunction "1_1") (pintype "passive"))
      (node (ref "R5") (pin "2") (pinfunction "2_2") (pintype "passive"))
      (node (ref "U1") (pin "4") (pinfunction "VBAT_4") (pintype "power_in"))
      (node (ref "U1") (pin "5") (pinfunction "VREF+_5") (pintype "power_in"))
      (node (ref "U1") (pin "6") (pinfunction "VDD/VDDA_6") (pintype "power_in"))
      (node (ref "U2") (pin "39") (pinfunction "DVDD_39") (pintype "power_in"))
    )
    (net (code "38") (name "VSSA") (class "Default")
      (node (ref "AO") (pin "2") (pinfunction "K_2") (pintype "passive"))
      (node (ref "C1") (pin "2") (pinfunction "2_2") (pintype "passive"))
      (node (ref "C12") (pin "-") (pinfunction "-_-") (pintype "passive"))
      (node (ref "C13") (pin "2") (pinfunction "2_2") (pintype "passive"))
      (node (ref "C14") (pin "2") (pinfunction "2_2") (pintype "passive"))
      (node (ref "C15") (pin "+") (pinfunction "+_+") (pintype "passive"))
      (node (ref "C16") (pin "2") (pinfunction "2_2") (pintype "passive"))
      (node (ref "C17") (pin "2") (pinfunction "2_2") (pintype "passive"))
      (node (ref "C18") (pin "2") (pinfunction "2_2") (pintype "passive"))
      (node (ref "C19") (pin "2") (pinfunction "2_2") (pintype "passive"))
      (node (ref "C2") (pin "2") (pinfunction "-_2") (pintype "passive"))
      (node (ref "C20") (pin "2") (pinfunction "2_2") (pintype "passive"))
      (node (ref "C21") (pin "2") (pinfunction "2_2") (pintype "passive"))
      (node (ref "C22") (pin "2") (pinfunction "2_2") (pintype "passive"))
      (node (ref "C23") (pin "2") (pinfunction "2_2") (pintype "passive"))
      (node (ref "C24") (pin "2") (pinfunction "2_2") (pintype "passive"))
      (node (ref "C25") (pin "2") (pinfunction "2_2") (pintype "passive"))
      (node (ref "C29") (pin "1") (pinfunction "1_1") (pintype "passive"))
      (node (ref "C3") (pin "2") (pinfunction "2_2") (pintype "passive"))
      (node (ref "C30") (pin "2") (pinfunction "2_2") (pintype "passive"))
      (node (ref "C31") (pin "2") (pinfunction "2_2") (pintype "passive"))
      (node (ref "C32") (pin "2") (pinfunction "2_2") (pintype "passive"))
      (node (ref "C33") (pin "2") (pinfunction "2_2") (pintype "passive"))
      (node (ref "C34") (pin "2") (pinfunction "2_2") (pintype "passive"))
      (node (ref "C4") (pin "2") (pinfunction "-_2") (pintype "passive"))
      (node (ref "PWR") (pin "2") (pinfunction "K_2") (pintype "passive"))
      (node (ref "R2") (pin "2") (pinfunction "2_2") (pintype "passive"))
      (node (ref "TVS1") (pin "A") (pinfunction "1_A") (pintype "passive"))
      (node (ref "TVS2") (pin "C") (pinfunction "2_C") (pintype "passive"))
      (node (ref "U1") (pin "7") (pinfunction "VSS/VSSA_7") (pintype "passive"))
      (node (ref "U2") (pin "12") (pinfunction "GND_3_12") (pintype "power_in"))
      (node (ref "U2") (pin "13") (pinfunction "GND_4_13") (pintype "power_in"))
      (node (ref "U2") (pin "15") (pinfunction "GND_15") (pintype "power_in"))
      (node (ref "U2") (pin "23") (pinfunction "DVDD-EN_23") (pintype "input"))
      (node (ref "U2") (pin "3") (pinfunction "GND_2_3") (pintype "power_in"))
      (node (ref "U2") (pin "34") (pinfunction "-VSENSE_34") (pintype "input"))
      (node (ref "U2") (pin "4") (pinfunction "CLR-SEL_4") (pintype "input"))
      (node (ref "U2") (pin "5") (pinfunction "CLR_5") (pintype "input"))
    )
    (net (code "39") (name "unconnected-(U1-PA0-Pad11)") (class "Default")
      (node (ref "U1") (pin "11") (pinfunction "PA0_11") (pintype "bidirectional"))
    )
    (net (code "40") (name "unconnected-(U1-PA1-Pad12)") (class "Default")
      (node (ref "U1") (pin "12") (pinfunction "PA1_12") (pintype "bidirectional"))
    )
    (net (code "41") (name "unconnected-(U1-PA4-Pad15)") (class "Default")
      (node (ref "U1") (pin "15") (pinfunction "PA4_15") (pintype "bidirectional"))
    )
    (net (code "42") (name "unconnected-(U1-PA5-Pad16)") (class "Default")
      (node (ref "U1") (pin "16") (pinfunction "PA5_16") (pintype "bidirectional"))
    )
    (net (code "43") (name "unconnected-(U1-PA6-Pad17)") (class "Default")
      (node (ref "U1") (pin "17") (pinfunction "PA6_17") (pintype "bidirectional"))
    )
    (net (code "44") (name "unconnected-(U1-PB1-Pad20)") (class "Default")
      (node (ref "U1") (pin "20") (pinfunction "PB1_20") (pintype "bidirectional"))
    )
    (net (code "45") (name "unconnected-(U1-PB2-Pad21)") (class "Default")
      (node (ref "U1") (pin "21") (pinfunction "PB2_21") (pintype "bidirectional"))
    )
    (net (code "46") (name "unconnected-(U1-PB3-Pad42)") (class "Default")
      (node (ref "U1") (pin "42") (pinfunction "PB3_42") (pintype "bidirectional"))
    )
    (net (code "47") (name "unconnected-(U1-PB4-Pad43)") (class "Default")
      (node (ref "U1") (pin "43") (pinfunction "PB4_43") (pintype "bidirectional"))
    )
    (net (code "48") (name "unconnected-(U1-PB5-Pad44)") (class "Default")
      (node (ref "U1") (pin "44") (pinfunction "PB5_44") (pintype "bidirectional"))
    )
    (net (code "49") (name "unconnected-(U1-PB6-Pad45)") (class "Default")
      (node (ref "U1") (pin "45") (pinfunction "PB6_45") (pintype "bidirectional"))
    )
    (net (code "50") (name "unconnected-(U1-PB7-Pad46)") (class "Default")
      (node (ref "U1") (pin "46") (pinfunction "PB7_46") (pintype "bidirectional"))
    )
    (net (code "51") (name "unconnected-(U1-PB8-Pad47)") (class "Default")
      (node (ref "U1") (pin "47") (pinfunction "PB8_47") (pintype "bidirectional"))
    )
    (net (code "52") (name "unconnected-(U1-PB12-Pad24)") (class "Default")
      (node (ref "U1") (pin "24") (pinfunction "PB12_24") (pintype "bidirectional"))
    )
    (net (code "53") (name "unconnected-(U1-PC15-OSC32_OUT-Pad3)") (class "Default")
      (node (ref "U1") (pin "3") (pinfunction "PC15-OSC32_OUT_3") (pintype "bidirectional"))
    )
    (net (code "54") (name "unconnected-(U1-PD1-Pad39)") (class "Default")
      (node (ref "U1") (pin "39") (pinfunction "PD1_39") (pintype "bidirectional"))
    )
    (net (code "55") (name "unconnected-(U2-BOOST-Pad27)") (class "Default")
      (node (ref "U2") (pin "27") (pinfunction "BOOST_27") (pintype "output"))
    )
    (net (code "56") (name "unconnected-(U2-ISET-R-Pad16)") (class "Default")
      (node (ref "U2") (pin "16") (pinfunction "ISET-R_16") (pintype "input"))
    )
    (net (code "57") (name "unconnected-(U2-NC-Pad40)") (class "Default")
      (node (ref "U2") (pin "40") (pinfunction "NC_40") (pintype "passive"))
    )
    (net (code "58") (name "unconnected-(U2-NC_2-Pad1)") (class "Default")
      (node (ref "U2") (pin "1") (pinfunction "NC_2_1") (pintype "passive"))
    )
    (net (code "59") (name "unconnected-(U2-NC_3-Pad10)") (class "Default")
      (node (ref "U2") (pin "10") (pinfunction "NC_3_10") (pintype "passive"))
    )
    (net (code "60") (name "unconnected-(U2-NC_4-Pad11)") (class "Default")
      (node (ref "U2") (pin "11") (pinfunction "NC_4_11") (pintype "passive"))
    )
    (net (code "61") (name "unconnected-(U2-NC_5-Pad19)") (class "Default")
      (node (ref "U2") (pin "19") (pinfunction "NC_5_19") (pintype "passive"))
    )
    (net (code "62") (name "unconnected-(U2-NC_6-Pad20)") (class "Default")
      (node (ref "U2") (pin "20") (pinfunction "NC_6_20") (pintype "passive"))
    )
    (net (code "63") (name "unconnected-(U2-NC_7-Pad21)") (class "Default")
      (node (ref "U2") (pin "21") (pinfunction "NC_7_21") (pintype "passive"))
    )
    (net (code "64") (name "unconnected-(U2-NC_8-Pad22)") (class "Default")
      (node (ref "U2") (pin "22") (pinfunction "NC_8_22") (pintype "passive"))
    )
    (net (code "65") (name "unconnected-(U2-NC_9-Pad30)") (class "Default")
      (node (ref "U2") (pin "30") (pinfunction "NC_9_30") (pintype "passive"))
    )
    (net (code "66") (name "unconnected-(U2-NC_10-Pad31)") (class "Default")
      (node (ref "U2") (pin "31") (pinfunction "NC_10_31") (pintype "passive"))
    )
    (net (code "67") (name "unconnected-(U2-NC_11-Pad35)") (class "Default")
      (node (ref "U2") (pin "35") (pinfunction "NC_11_35") (pintype "passive"))
    )
    (net (code "68") (name "unconnected-(U2-NC_12-Pad38)") (class "Default")
      (node (ref "U2") (pin "38") (pinfunction "NC_12_38") (pintype "passive"))
    )
  )
)
